# 01_Power.net
KiCad netlist of a schematic drawn in Altium Designer
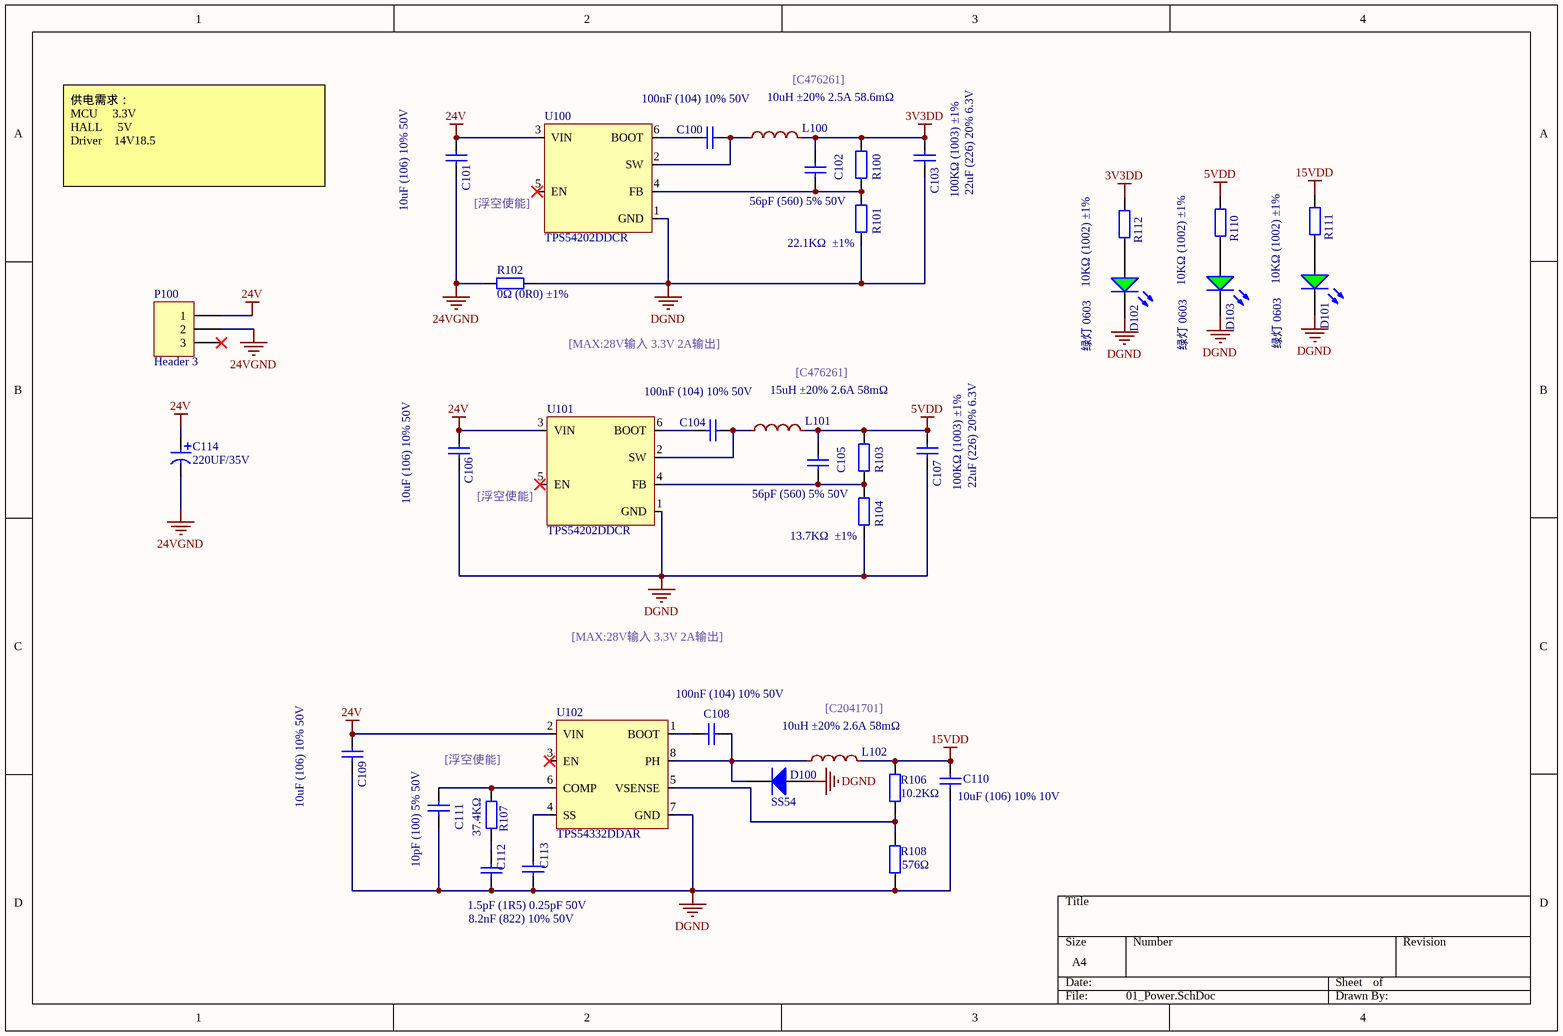
[diagram p0: 01_Power.SchDoc]

(export (version "E")
  (design (tool "Eeschema 10.0.6"))
  (components
    (comp (ref "C100")
      (value "100nF (104) 10% 50V")
      (footprint "0603_C")
      (description "贴片电容")
      (libsource (lib "Miscellaneous Devices LC") (part "0603 100nF (104) 10% 50V"))
    )
    (comp (ref "C101")
      (value "10uF (106) 10% 50V")
      (footprint "0603_C")
      (description "贴片电容")
      (libsource (lib "Miscellaneous Devices LC") (part "0603 10uF (106) 10% 10V"))
    )
    (comp (ref "C102")
      (value "56pF (560) 5% 50V")
      (footprint "0603_C")
      (description "贴片电容")
      (libsource (lib "Miscellaneous Devices LC") (part "0603 56pF (560) 5% 50V"))
    )
    (comp (ref "C103")
      (value "22uF (226) 20% 6.3V")
      (footprint "0603_C")
      (description "贴片电容")
      (libsource (lib "Miscellaneous Devices LC") (part "0603 22uF (226) 20% 6.3V"))
    )
    (comp (ref "C104")
      (value "100nF (104) 10% 50V")
      (footprint "0603_C")
      (description "贴片电容")
      (libsource (lib "Miscellaneous Devices LC") (part "0603 100nF (104) 10% 50V"))
    )
    (comp (ref "C105")
      (value "56pF (560) 5% 50V")
      (footprint "0603_C")
      (description "贴片电容")
      (libsource (lib "Miscellaneous Devices LC") (part "0603 56pF (560) 5% 50V"))
    )
    (comp (ref "C106")
      (value "10uF (106) 10% 50V")
      (footprint "0603_C")
      (description "贴片电容")
      (libsource (lib "Miscellaneous Devices LC") (part "0603 10uF (106) 10% 10V"))
    )
    (comp (ref "C107")
      (value "22uF (226) 20% 6.3V")
      (footprint "0603_C")
      (description "贴片电容")
      (libsource (lib "Miscellaneous Devices LC") (part "0603 22uF (226) 20% 6.3V"))
    )
    (comp (ref "C108")
      (value "100nF (104) 10% 50V")
      (footprint "0603_C")
      (description "贴片电容")
      (libsource (lib "Miscellaneous Devices LC") (part "0603 100nF (104) 10% 50V"))
    )
    (comp (ref "C109")
      (value "10uF (106) 10% 50V")
      (footprint "0603_C")
      (description "贴片电容")
      (libsource (lib "Miscellaneous Devices LC") (part "0603 10uF (106) 10% 10V"))
    )
    (comp (ref "C110")
      (value "10uF (106) 10% 10V")
      (footprint "0603_C")
      (description "贴片电容")
      (libsource (lib "Miscellaneous Devices LC") (part "0603 10uF (106) 10% 10V"))
    )
    (comp (ref "C111")
      (value "10pF (100) 5% 50V")
      (footprint "0603_C")
      (description "贴片电容")
      (libsource (lib "Miscellaneous Devices LC") (part "0603 10pF (100) 5% 50V"))
    )
    (comp (ref "C112")
      (value "1.5pF (1R5) 0.25pF 50V")
      (footprint "0603_C")
      (description "贴片电容")
      (libsource (lib "Miscellaneous Devices LC") (part "0603 1.5pF (1R5) 0.25pF 50V"))
    )
    (comp (ref "C113")
      (value "8.2nF (822) 10% 50V")
      (footprint "0603_C")
      (description "贴片电容")
      (libsource (lib "Miscellaneous Devices LC") (part "0603 8.2nF (822) 10% 50V"))
    )
    (comp (ref "C114")
      (value "220UF/35V")
      (footprint "CAP_L8.3_W8.3")
      (description "电解电容")
      (libsource (lib "Schlibv2") (part "CAP2"))
    )
    (comp (ref "D100")
      (value "SS54")
      (footprint "SMA(DO-214AC)_S1")
      (description "二极管")
      (libsource (lib "Miscellaneous Devices LC") (part "SMA(DO-214AC) SS54"))
    )
    (comp (ref "D101")
      (value "绿灯 0603")
      (footprint "0603_LED_S1")
      (description "发光二极管")
      (libsource (lib "Miscellaneous Devices LC") (part "0603 绿灯"))
    )
    (comp (ref "D102")
      (value "绿灯 0603")
      (footprint "0603_LED_S1")
      (description "发光二极管")
      (libsource (lib "Miscellaneous Devices LC") (part "0603 绿灯"))
    )
    (comp (ref "D103")
      (value "绿灯 0603")
      (footprint "0603_LED_S1")
      (description "发光二极管")
      (libsource (lib "Miscellaneous Devices LC") (part "0603 绿灯"))
    )
    (comp (ref "L100")
      (value "10uH ±20% 2.5A 58.6mΩ")
      (footprint "L_SMD_L6_W6")
      (libsource (lib "Schlibv2") (part "L"))
    )
    (comp (ref "L101")
      (value "15uH ±20% 2.6A 58mΩ")
      (footprint "L_SMD_L8_W8")
      (libsource (lib "Schlibv2") (part "L"))
    )
    (comp (ref "L102")
      (value "10uH ±20% 2.6A 58mΩ")
      (footprint "L_SMD_L6_W6")
      (libsource (lib "Schlibv2") (part "L"))
    )
    (comp (ref "P100")
      (value "Header 3")
      (footprint "KF2EDGK-3.81-WI-3P")
      (description "Header, 3-Pin")
      (fields (field (name "PUBLISHER") "Altium Limited"))
      (libsource (lib "Miscellaneous Connectors") (part "Header 3"))
    )
    (comp (ref "R100")
      (value "100KΩ (1003) ±1%")
      (footprint "0603_R")
      (description "贴片电阻")
      (libsource (lib "Miscellaneous Devices LC") (part "0603 100KΩ (1003) 1%"))
    )
    (comp (ref "R101")
      (value "22.1KΩ  ±1%")
      (footprint "0603_R")
      (description "贴片电阻")
      (libsource (lib "Miscellaneous Devices LC") (part "0603 100KΩ (1003) 1%"))
    )
    (comp (ref "R102")
      (value "0Ω (0R0) ±1%")
      (footprint "LC-0805")
      (description "贴片电阻")
      (libsource (lib "Miscellaneous Devices LC") (part "0603 0Ω (0R0) 1%"))
    )
    (comp (ref "R103")
      (value "100KΩ (1003) ±1%")
      (footprint "0603_R")
      (description "贴片电阻")
      (libsource (lib "Miscellaneous Devices LC") (part "0603 100KΩ (1003) 1%"))
    )
    (comp (ref "R104")
      (value "13.7KΩ  ±1%")
      (footprint "0603_R")
      (description "贴片电阻")
      (libsource (lib "Miscellaneous Devices LC") (part "0603 100KΩ (1003) 1%"))
    )
    (comp (ref "R106")
      (value "10.2KΩ")
      (footprint "0603_R")
      (description "贴片电阻")
      (libsource (lib "Miscellaneous Devices LC") (part "0603 10KΩ (1002) 1%"))
    )
    (comp (ref "R107")
      (value "37.4KΩ")
      (footprint "0603_R")
      (description "贴片电阻")
      (libsource (lib "Miscellaneous Devices LC") (part "0603 10KΩ (1002) 1%"))
    )
    (comp (ref "R108")
      (value "576Ω")
      (footprint "0603_R")
      (description "贴片电阻")
      (libsource (lib "Miscellaneous Devices LC") (part "0603 10KΩ (1002) 1%"))
    )
    (comp (ref "R110")
      (value "10KΩ (1002) ±1%")
      (footprint "0603_R")
      (description "贴片电阻")
      (libsource (lib "Miscellaneous Devices LC") (part "0603 10KΩ (1002) 1%"))
    )
    (comp (ref "R111")
      (value "10KΩ (1002) ±1%")
      (footprint "0603_R")
      (description "贴片电阻")
      (libsource (lib "Miscellaneous Devices LC") (part "0603 10KΩ (1002) 1%"))
    )
    (comp (ref "R112")
      (value "10KΩ (1002) ±1%")
      (footprint "0603_R")
      (description "贴片电阻")
      (libsource (lib "Miscellaneous Devices LC") (part "0603 10KΩ (1002) 1%"))
    )
    (comp (ref "U100")
      (value "TPS54202DDCR")
      (footprint "TPS54202DDCR")
      (libsource (lib "Schlibv2") (part "TPS54202DDCR"))
    )
    (comp (ref "U101")
      (value "TPS54202DDCR")
      (footprint "TPS54202DDCR")
      (libsource (lib "Schlibv2") (part "TPS54202DDCR"))
    )
    (comp (ref "U102")
      (value "TPS54332DDAR")
      (footprint "TPS54332DDAR")
      (libsource (lib "Schlibv2") (part "TPS54332DDAR"))
    )
  )
  (nets
    (net (code "1") (name "3V3DD") (class "Default")
      (node (ref "C102") (pin "2") (pinfunction "2_2") (pintype "passive"))
      (node (ref "C103") (pin "2") (pinfunction "2_2") (pintype "passive"))
      (node (ref "L100") (pin "2") (pinfunction "2_2") (pintype "passive"))
      (node (ref "R100") (pin "2") (pinfunction "2_2") (pintype "passive"))
      (node (ref "R112") (pin "2") (pinfunction "2_2") (pintype "passive"))
    )
    (net (code "2") (name "5VDD") (class "Default")
      (node (ref "C105") (pin "2") (pinfunction "2_2") (pintype "passive"))
      (node (ref "C107") (pin "2") (pinfunction "2_2") (pintype "passive"))
      (node (ref "L101") (pin "2") (pinfunction "2_2") (pintype "passive"))
      (node (ref "R103") (pin "2") (pinfunction "2_2") (pintype "passive"))
      (node (ref "R110") (pin "2") (pinfunction "2_2") (pintype "passive"))
    )
    (net (code "3") (name "15VDD") (class "Default")
      (node (ref "C110") (pin "1") (pinfunction "1_1") (pintype "passive"))
      (node (ref "L102") (pin "2") (pinfunction "2_2") (pintype "passive"))
      (node (ref "R106") (pin "2") (pinfunction "2_2") (pintype "passive"))
      (node (ref "R111") (pin "2") (pinfunction "2_2") (pintype "passive"))
    )
    (net (code "4") (name "24V") (class "Default")
      (node (ref "C101") (pin "2") (pinfunction "2_2") (pintype "passive"))
      (node (ref "C106") (pin "2") (pinfunction "2_2") (pintype "passive"))
      (node (ref "C109") (pin "2") (pinfunction "2_2") (pintype "passive"))
      (node (ref "C114") (pin "1") (pintype "passive"))
      (node (ref "P100") (pin "1") (pinfunction "1_1") (pintype "passive"))
      (node (ref "U100") (pin "3") (pinfunction "VIN_3") (pintype "passive"))
      (node (ref "U101") (pin "3") (pinfunction "VIN_3") (pintype "passive"))
      (node (ref "U102") (pin "2") (pinfunction "VIN_2") (pintype "passive"))
    )
    (net (code "5") (name "24VGND") (class "Default")
      (node (ref "C101") (pin "1") (pinfunction "1_1") (pintype "passive"))
      (node (ref "C114") (pin "2") (pintype "passive"))
      (node (ref "P100") (pin "2") (pinfunction "2_2") (pintype "passive"))
      (node (ref "R102") (pin "1") (pinfunction "1_1") (pintype "passive"))
    )
    (net (code "6") (name "DGND") (class "Default")
      (node (ref "C103") (pin "1") (pinfunction "1_1") (pintype "passive"))
      (node (ref "C106") (pin "1") (pinfunction "1_1") (pintype "passive"))
      (node (ref "C107") (pin "1") (pinfunction "1_1") (pintype "passive"))
      (node (ref "C109") (pin "1") (pinfunction "1_1") (pintype "passive"))
      (node (ref "C110") (pin "2") (pinfunction "2_2") (pintype "passive"))
      (node (ref "C111") (pin "1") (pinfunction "1_1") (pintype "passive"))
      (node (ref "C112") (pin "1") (pinfunction "1_1") (pintype "passive"))
      (node (ref "C113") (pin "1") (pinfunction "1_1") (pintype "passive"))
      (node (ref "D100") (pin "1") (pinfunction "A_1") (pintype "passive"))
      (node (ref "D101") (pin "K") (pinfunction "K_K") (pintype "passive"))
      (node (ref "D102") (pin "K") (pinfunction "K_K") (pintype "passive"))
      (node (ref "D103") (pin "K") (pinfunction "K_K") (pintype "passive"))
      (node (ref "R101") (pin "1") (pinfunction "1_1") (pintype "passive"))
      (node (ref "R102") (pin "2") (pinfunction "2_2") (pintype "passive"))
      (node (ref "R104") (pin "1") (pinfunction "1_1") (pintype "passive"))
      (node (ref "R108") (pin "1") (pinfunction "1_1") (pintype "passive"))
      (node (ref "U100") (pin "1") (pinfunction "GND_1") (pintype "passive"))
      (node (ref "U101") (pin "1") (pinfunction "GND_1") (pintype "passive"))
      (node (ref "U102") (pin "7") (pinfunction "GND_7") (pintype "passive"))
    )
    (net (code "7") (name "Net-(C112-Pad2)") (class "Default")
      (node (ref "C112") (pin "2") (pinfunction "2_2") (pintype "passive"))
      (node (ref "R107") (pin "1") (pinfunction "1_1") (pintype "passive"))
    )
    (net (code "8") (name "Net-(D100-K)") (class "Default")
      (node (ref "C108") (pin "2") (pinfunction "2_2") (pintype "passive"))
      (node (ref "D100") (pin "2") (pinfunction "K_2") (pintype "passive"))
      (node (ref "L102") (pin "1") (pinfunction "1_1") (pintype "passive"))
      (node (ref "U102") (pin "8") (pinfunction "PH_8") (pintype "passive"))
    )
    (net (code "9") (name "Net-(D101-PadA)") (class "Default")
      (node (ref "D101") (pin "A") (pinfunction "A_A") (pintype "passive"))
      (node (ref "R111") (pin "1") (pinfunction "1_1") (pintype "passive"))
    )
    (net (code "10") (name "Net-(D102-PadA)") (class "Default")
      (node (ref "D102") (pin "A") (pinfunction "A_A") (pintype "passive"))
      (node (ref "R112") (pin "1") (pinfunction "1_1") (pintype "passive"))
    )
    (net (code "11") (name "Net-(D103-PadA)") (class "Default")
      (node (ref "D103") (pin "A") (pinfunction "A_A") (pintype "passive"))
      (node (ref "R110") (pin "1") (pinfunction "1_1") (pintype "passive"))
    )
    (net (code "12") (name "Net-(U100-BOOT)") (class "Default")
      (node (ref "C100") (pin "1") (pinfunction "1_1") (pintype "passive"))
      (node (ref "U100") (pin "6") (pinfunction "BOOT_6") (pintype "passive"))
    )
    (net (code "13") (name "Net-(U100-FB)") (class "Default")
      (node (ref "C102") (pin "1") (pinfunction "1_1") (pintype "passive"))
      (node (ref "R100") (pin "1") (pinfunction "1_1") (pintype "passive"))
      (node (ref "R101") (pin "2") (pinfunction "2_2") (pintype "passive"))
      (node (ref "U100") (pin "4") (pinfunction "FB_4") (pintype "passive"))
    )
    (net (code "14") (name "Net-(U100-SW)") (class "Default")
      (node (ref "C100") (pin "2") (pinfunction "2_2") (pintype "passive"))
      (node (ref "L100") (pin "1") (pinfunction "1_1") (pintype "passive"))
      (node (ref "U100") (pin "2") (pinfunction "SW_2") (pintype "passive"))
    )
    (net (code "15") (name "Net-(U101-BOOT)") (class "Default")
      (node (ref "C104") (pin "1") (pinfunction "1_1") (pintype "passive"))
      (node (ref "U101") (pin "6") (pinfunction "BOOT_6") (pintype "passive"))
    )
    (net (code "16") (name "Net-(U101-FB)") (class "Default")
      (node (ref "C105") (pin "1") (pinfunction "1_1") (pintype "passive"))
      (node (ref "R103") (pin "1") (pinfunction "1_1") (pintype "passive"))
      (node (ref "R104") (pin "2") (pinfunction "2_2") (pintype "passive"))
      (node (ref "U101") (pin "4") (pinfunction "FB_4") (pintype "passive"))
    )
    (net (code "17") (name "Net-(U101-SW)") (class "Default")
      (node (ref "C104") (pin "2") (pinfunction "2_2") (pintype "passive"))
      (node (ref "L101") (pin "1") (pinfunction "1_1") (pintype "passive"))
      (node (ref "U101") (pin "2") (pinfunction "SW_2") (pintype "passive"))
    )
    (net (code "18") (name "Net-(U102-BOOT)") (class "Default")
      (node (ref "C108") (pin "1") (pinfunction "1_1") (pintype "passive"))
      (node (ref "U102") (pin "1") (pinfunction "BOOT_1") (pintype "passive"))
    )
    (net (code "19") (name "Net-(U102-COMP)") (class "Default")
      (node (ref "C111") (pin "2") (pinfunction "2_2") (pintype "passive"))
      (node (ref "R107") (pin "2") (pinfunction "2_2") (pintype "passive"))
      (node (ref "U102") (pin "6") (pinfunction "COMP_6") (pintype "passive"))
    )
    (net (code "20") (name "Net-(U102-SS)") (class "Default")
      (node (ref "C113") (pin "2") (pinfunction "2_2") (pintype "passive"))
      (node (ref "U102") (pin "4") (pinfunction "SS_4") (pintype "passive"))
    )
    (net (code "21") (name "Net-(U102-VSENSE)") (class "Default")
      (node (ref "R106") (pin "1") (pinfunction "1_1") (pintype "passive"))
      (node (ref "R108") (pin "2") (pinfunction "2_2") (pintype "passive"))
      (node (ref "U102") (pin "5") (pinfunction "VSENSE_5") (pintype "passive"))
    )
    (net (code "22") (name "unconnected-(P100-Pad3)") (class "Default")
      (node (ref "P100") (pin "3") (pinfunction "3_3") (pintype "passive+no_connect"))
    )
    (net (code "23") (name "unconnected-(U100-EN-Pad5)") (class "Default")
      (node (ref "U100") (pin "5") (pinfunction "EN_5") (pintype "passive+no_connect"))
    )
    (net (code "24") (name "unconnected-(U101-EN-Pad5)") (class "Default")
      (node (ref "U101") (pin "5") (pinfunction "EN_5") (pintype "passive+no_connect"))
    )
    (net (code "25") (name "unconnected-(U102-EN-Pad3)") (class "Default")
      (node (ref "U102") (pin "3") (pinfunction "EN_3") (pintype "passive+no_connect"))
    )
  )
)
